# FSK-Modulator-V1.net
KiCad netlist of a schematic drawn in Altium Designer
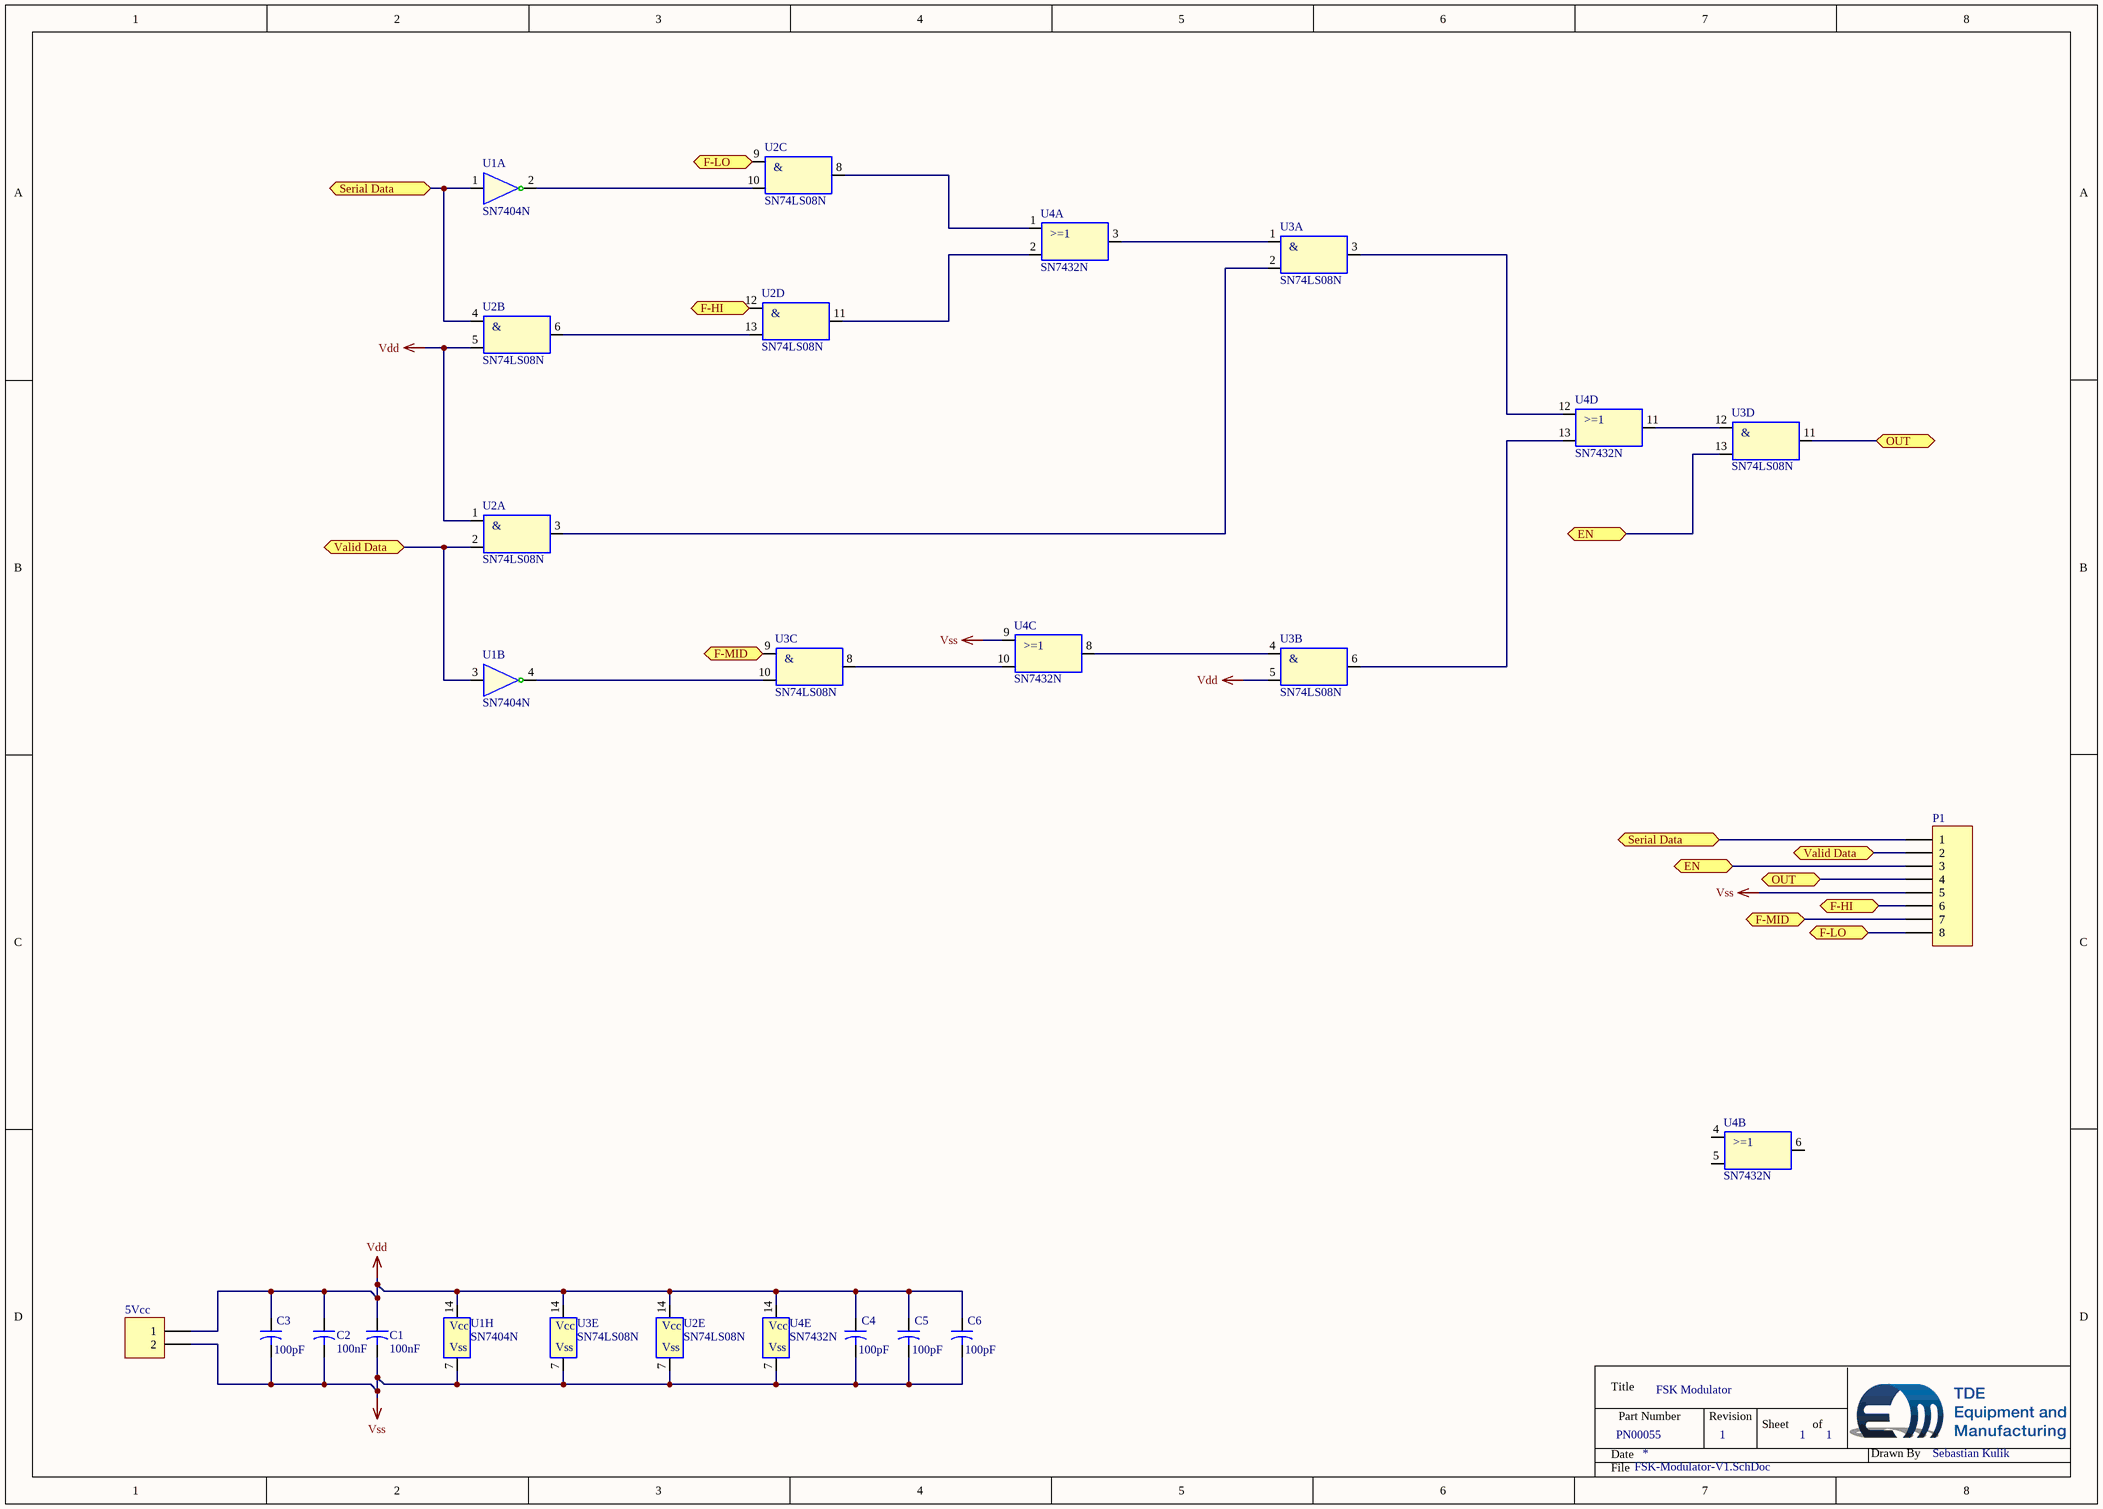
[diagram p0: FSK-Modulator-V1.SchDoc]

(export (version "E")
  (design (tool "Eeschema 10.0.6"))
  (components
    (comp (ref "5Vcc")
      (value "PHOENIX_1715721")
      (footprint "Phoenix-2-5_08")
      (description "Phoenix, 2 pol, 5.08mm, 22A, 715721")
      (fields (field (name "MANUFACTURER") "Phoenix") (field (name "PUBLISHER") "Sebastian Kulik"))
      (libsource (lib "Connectors") (part "2Pol_1715721"))
    )
    (comp (ref "C1")
      (value "100nF")
      (footprint "Dummy-10mm")
      (description "Capacitor-Dummy-THT")
      (fields (field (name "PUBLISHER") "Sebastian Kulik"))
      (libsource (lib "Capacitors") (part "Capacitor-Dummy-THT"))
    )
    (comp (ref "C2")
      (value "100nF")
      (footprint "Dummy-10mm")
      (description "Capacitor-Dummy-THT")
      (fields (field (name "PUBLISHER") "Sebastian Kulik"))
      (libsource (lib "Capacitors") (part "Capacitor-Dummy-THT"))
    )
    (comp (ref "C3")
      (value "100pF")
      (footprint "Dummy-10mm")
      (description "Capacitor-Dummy-THT")
      (fields (field (name "PUBLISHER") "Sebastian Kulik"))
      (libsource (lib "Capacitors") (part "Capacitor-Dummy-THT"))
    )
    (comp (ref "C4")
      (value "100pF")
      (footprint "Dummy-10mm")
      (description "Capacitor-Dummy-THT")
      (fields (field (name "PUBLISHER") "Sebastian Kulik"))
      (libsource (lib "Capacitors") (part "Capacitor-Dummy-THT"))
    )
    (comp (ref "C5")
      (value "100pF")
      (footprint "Dummy-10mm")
      (description "Capacitor-Dummy-THT")
      (fields (field (name "PUBLISHER") "Sebastian Kulik"))
      (libsource (lib "Capacitors") (part "Capacitor-Dummy-THT"))
    )
    (comp (ref "C6")
      (value "100pF")
      (footprint "Dummy-10mm")
      (description "Capacitor-Dummy-THT")
      (fields (field (name "PUBLISHER") "Sebastian Kulik"))
      (libsource (lib "Capacitors") (part "Capacitor-Dummy-THT"))
    )
    (comp (ref "P1")
      (value "Plug_08_2.54")
      (footprint "HDR1X8_2.54")
      (description "Plug, 08-Pin")
      (fields (field (name "MANUFACTURER") "WE") (field (name "PUBLISHER") "Sebastian Kulik"))
      (libsource (lib "Connectors") (part "Plug_08_2.54"))
    )
    (comp (ref "U1")
      (value "SN7404N")
      (footprint "DIP-14")
      (description "Hex Inverter TTL")
      (fields (field (name "MANUFACTURER") "TI") (field (name "PUBLISHER") "Sebastian Kulik"))
      (libsource (lib "ICs") (part "SN7404N"))
    )
    (comp (ref "U2")
      (value "SN74LS08N")
      (footprint "DIP-14")
      (description "Quad AND, TTL")
      (fields (field (name "MANUFACTURER") "TI") (field (name "PUBLISHER") "Sebastian Kulik"))
      (libsource (lib "") (part "SN74LS08N_1"))
    )
    (comp (ref "U3")
      (value "SN74LS08N")
      (footprint "DIP-14")
      (description "Quad AND, TTL")
      (fields (field (name "MANUFACTURER") "TI") (field (name "PUBLISHER") "Sebastian Kulik"))
      (libsource (lib "") (part "SN74LS08N_1"))
    )
    (comp (ref "U4")
      (value "SN7432N")
      (footprint "DIP-14")
      (description "Quad NAND, TTL")
      (fields (field (name "MANUFACTURER") "TI") (field (name "PUBLISHER") "Sebastian Kulik"))
      (libsource (lib "ICs") (part "SN7432N"))
    )
  )
  (nets
    (net (code "1") (name "/EN") (class "Default")
      (node (ref "P1") (pin "3") (pinfunction "3_3") (pintype "passive"))
      (node (ref "U3") (pin "13") (pinfunction "4B_13") (pintype "passive"))
    )
    (net (code "2") (name "/F-HI") (class "Default")
      (node (ref "P1") (pin "6") (pinfunction "6_6") (pintype "passive"))
      (node (ref "U2") (pin "12") (pinfunction "4A_12") (pintype "passive"))
    )
    (net (code "3") (name "/F-LO") (class "Default")
      (node (ref "P1") (pin "8") (pinfunction "8_8") (pintype "passive"))
      (node (ref "U2") (pin "9") (pinfunction "3A_9") (pintype "passive"))
    )
    (net (code "4") (name "/F-MID") (class "Default")
      (node (ref "P1") (pin "7") (pinfunction "7_7") (pintype "passive"))
      (node (ref "U3") (pin "9") (pinfunction "3A_9") (pintype "passive"))
    )
    (net (code "5") (name "/OUT") (class "Default")
      (node (ref "P1") (pin "4") (pinfunction "4_4") (pintype "passive"))
      (node (ref "U3") (pin "11") (pinfunction "Y4_11") (pintype "passive"))
    )
    (net (code "6") (name "/Serial Data") (class "Default")
      (node (ref "P1") (pin "1") (pinfunction "1_1") (pintype "passive"))
      (node (ref "U1") (pin "1") (pinfunction "1A_1") (pintype "passive"))
      (node (ref "U2") (pin "4") (pinfunction "2A_4") (pintype "passive"))
    )
    (net (code "7") (name "/Valid Data") (class "Default")
      (node (ref "P1") (pin "2") (pinfunction "2_2") (pintype "passive"))
      (node (ref "U1") (pin "3") (pinfunction "2A_3") (pintype "passive"))
      (node (ref "U2") (pin "2") (pinfunction "1B_2") (pintype "passive"))
    )
    (net (code "8") (name "Net-(U1A-1Y)") (class "Default")
      (node (ref "U1") (pin "2") (pinfunction "1Y_2") (pintype "passive"))
      (node (ref "U2") (pin "10") (pinfunction "3B_10") (pintype "passive"))
    )
    (net (code "9") (name "Net-(U1B-2Y)") (class "Default")
      (node (ref "U1") (pin "4") (pinfunction "2Y_4") (pintype "passive"))
      (node (ref "U3") (pin "10") (pinfunction "3B_10") (pintype "passive"))
    )
    (net (code "10") (name "Net-(U2A-Y1)") (class "Default")
      (node (ref "U2") (pin "3") (pinfunction "Y1_3") (pintype "passive"))
      (node (ref "U3") (pin "2") (pinfunction "1B_2") (pintype "passive"))
    )
    (net (code "11") (name "Net-(U2B-Y2)") (class "Default")
      (node (ref "U2") (pin "13") (pinfunction "4B_13") (pintype "passive"))
      (node (ref "U2") (pin "6") (pinfunction "Y2_6") (pintype "passive"))
    )
    (net (code "12") (name "Net-(U2C-Y3)") (class "Default")
      (node (ref "U2") (pin "8") (pinfunction "Y3_8") (pintype "passive"))
      (node (ref "U4") (pin "1") (pinfunction "1A_1") (pintype "passive"))
    )
    (net (code "13") (name "Net-(U2D-Y4)") (class "Default")
      (node (ref "U2") (pin "11") (pinfunction "Y4_11") (pintype "passive"))
      (node (ref "U4") (pin "2") (pinfunction "1B_2") (pintype "passive"))
    )
    (net (code "14") (name "Net-(U3A-1A)") (class "Default")
      (node (ref "U3") (pin "1") (pinfunction "1A_1") (pintype "passive"))
      (node (ref "U4") (pin "3") (pinfunction "Y1_3") (pintype "passive"))
    )
    (net (code "15") (name "Net-(U3A-Y1)") (class "Default")
      (node (ref "U3") (pin "3") (pinfunction "Y1_3") (pintype "passive"))
      (node (ref "U4") (pin "12") (pinfunction "4A_12") (pintype "passive"))
    )
    (net (code "16") (name "Net-(U3B-2A)") (class "Default")
      (node (ref "U3") (pin "4") (pinfunction "2A_4") (pintype "passive"))
      (node (ref "U4") (pin "8") (pinfunction "Y3_8") (pintype "passive"))
    )
    (net (code "17") (name "Net-(U3B-Y2)") (class "Default")
      (node (ref "U3") (pin "6") (pinfunction "Y2_6") (pintype "passive"))
      (node (ref "U4") (pin "13") (pinfunction "4B_13") (pintype "passive"))
    )
    (net (code "18") (name "Net-(U3C-Y3)") (class "Default")
      (node (ref "U3") (pin "8") (pinfunction "Y3_8") (pintype "passive"))
      (node (ref "U4") (pin "10") (pinfunction "3B_10") (pintype "passive"))
    )
    (net (code "19") (name "Net-(U3D-4A)") (class "Default")
      (node (ref "U3") (pin "12") (pinfunction "4A_12") (pintype "passive"))
      (node (ref "U4") (pin "11") (pinfunction "Y4_11") (pintype "passive"))
    )
    (net (code "20") (name "Vdd") (class "Default")
      (node (ref "5Vcc") (pin "1") (pinfunction "1_1") (pintype "passive"))
      (node (ref "C1") (pin "1") (pinfunction "1_1") (pintype "passive"))
      (node (ref "C2") (pin "1") (pinfunction "1_1") (pintype "passive"))
      (node (ref "C3") (pin "1") (pinfunction "1_1") (pintype "passive"))
      (node (ref "C4") (pin "1") (pinfunction "1_1") (pintype "passive"))
      (node (ref "C5") (pin "1") (pinfunction "1_1") (pintype "passive"))
      (node (ref "C6") (pin "1") (pinfunction "1_1") (pintype "passive"))
      (node (ref "U1") (pin "14") (pinfunction "Vcc_14") (pintype "passive"))
      (node (ref "U2") (pin "1") (pinfunction "1A_1") (pintype "passive"))
      (node (ref "U2") (pin "14") (pinfunction "Vcc_14") (pintype "passive"))
      (node (ref "U2") (pin "5") (pinfunction "2B_5") (pintype "passive"))
      (node (ref "U3") (pin "14") (pinfunction "Vcc_14") (pintype "passive"))
      (node (ref "U3") (pin "5") (pinfunction "2B_5") (pintype "passive"))
      (node (ref "U4") (pin "14") (pinfunction "Vcc_14") (pintype "passive"))
    )
    (net (code "21") (name "Vss") (class "Default")
      (node (ref "5Vcc") (pin "2") (pinfunction "2_2") (pintype "passive"))
      (node (ref "C1") (pin "2") (pinfunction "2_2") (pintype "passive"))
      (node (ref "C2") (pin "2") (pinfunction "2_2") (pintype "passive"))
      (node (ref "C3") (pin "2") (pinfunction "2_2") (pintype "passive"))
      (node (ref "C4") (pin "2") (pinfunction "2_2") (pintype "passive"))
      (node (ref "C5") (pin "2") (pinfunction "2_2") (pintype "passive"))
      (node (ref "C6") (pin "2") (pinfunction "2_2") (pintype "passive"))
      (node (ref "P1") (pin "5") (pinfunction "5_5") (pintype "passive"))
      (node (ref "U1") (pin "7") (pinfunction "Vss_7") (pintype "passive"))
      (node (ref "U2") (pin "7") (pinfunction "Vss_7") (pintype "passive"))
      (node (ref "U3") (pin "7") (pinfunction "Vss_7") (pintype "passive"))
      (node (ref "U4") (pin "7") (pinfunction "Vss_7") (pintype "passive"))
      (node (ref "U4") (pin "9") (pinfunction "3A_9") (pintype "passive"))
    )
    (net (code "22") (name "unconnected-(U4B-2A-Pad4)") (class "Default")
      (node (ref "U4") (pin "4") (pinfunction "2A_4") (pintype "passive"))
    )
    (net (code "23") (name "unconnected-(U4B-2B-Pad5)") (class "Default")
      (node (ref "U4") (pin "5") (pinfunction "2B_5") (pintype "passive"))
    )
    (net (code "24") (name "unconnected-(U4B-Y2-Pad6)") (class "Default")
      (node (ref "U4") (pin "6") (pinfunction "Y2_6") (pintype "passive"))
    )
  )
)
